# ERC128128FS_Breakout.net
KiCad netlist of a schematic drawn in EAGLE
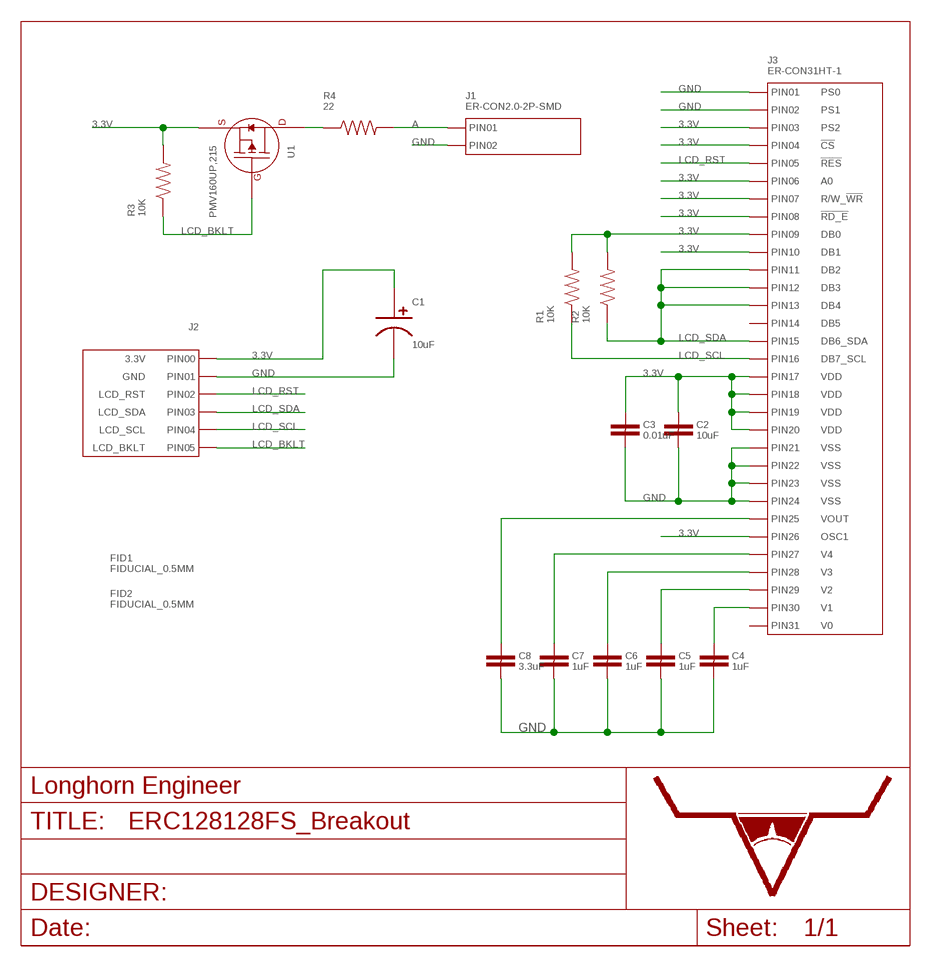
[diagram p0: schematic, sheet 1]

(export (version "E")
  (design (tool "Eeschema 10.0.6"))
  (components
    (comp (ref "C1")
      (value "10uF")
      (footprint "eagle-import:CP4MM")
      (libsource (lib "eagle-import") (part "CAPACITOR_P_4MM"))
    )
    (comp (ref "C2")
      (value "10uF")
      (footprint "eagle-import:1206")
      (libsource (lib "eagle-import") (part "CAPACITOR_NON_POLAR_1206"))
    )
    (comp (ref "C3")
      (value "0.01uF")
      (footprint "eagle-import:0603")
      (libsource (lib "eagle-import") (part "CAPACITOR_NON_POLAR_0603"))
    )
    (comp (ref "C4")
      (value "1uF")
      (footprint "eagle-import:0603")
      (libsource (lib "eagle-import") (part "CAPACITOR_NON_POLAR_0603"))
    )
    (comp (ref "C5")
      (value "1uF")
      (footprint "eagle-import:0603")
      (libsource (lib "eagle-import") (part "CAPACITOR_NON_POLAR_0603"))
    )
    (comp (ref "C6")
      (value "1uF")
      (footprint "eagle-import:0603")
      (libsource (lib "eagle-import") (part "CAPACITOR_NON_POLAR_0603"))
    )
    (comp (ref "C7")
      (value "1uF")
      (footprint "eagle-import:0603")
      (libsource (lib "eagle-import") (part "CAPACITOR_NON_POLAR_0603"))
    )
    (comp (ref "C8")
      (value "3.3uF")
      (footprint "eagle-import:0603")
      (libsource (lib "eagle-import") (part "CAPACITOR_NON_POLAR_0603"))
    )
    (comp (ref "FID1")
      (value "FIDUCIAL_0.5MM")
      (footprint "eagle-import:FIDUCIAL_0.5MM")
      (libsource (lib "eagle-import") (part "FIDUCIAL_0.5MM"))
    )
    (comp (ref "FID2")
      (value "FIDUCIAL_0.5MM")
      (footprint "eagle-import:FIDUCIAL_0.5MM")
      (libsource (lib "eagle-import") (part "FIDUCIAL_0.5MM"))
    )
    (comp (ref "J1")
      (value "ER-CON2.0-2P-SMD")
      (footprint "eagle-import:ER-CON2.0-2P-SMD")
      (libsource (lib "eagle-import") (part "CON_01X02_ER-CON2.0-2P-SMD"))
    )
    (comp (ref "J2")
      (value "HEADER_01X06_PTH_2.54MM")
      (footprint "eagle-import:PTH_2.54MM_01X06")
      (fields
        (field (name "LABEL00") "3.3V")
        (field (name "LABEL01") "GND")
        (field (name "LABEL02") "LCD_RST")
        (field (name "LABEL03") "LCD_SDA")
        (field (name "LABEL04") "LCD_SCL")
        (field (name "LABEL05") "LCD_BKLT")
      )
      (libsource (lib "eagle-import") (part "HEADER_01X06_PTH_2.54MM"))
    )
    (comp (ref "J3")
      (value "ER-CON31HT-1")
      (footprint "eagle-import:ER-CON31HT-1")
      (fields
        (field (name "LABEL01") "PS0")
        (field (name "LABEL02") "PS1")
        (field (name "LABEL03") "PS2")
        (field (name "LABEL04") "!CS")
        (field (name "LABEL05") "!RES")
        (field (name "LABEL06") "A0")
        (field (name "LABEL07") "R/W_!WR")
        (field (name "LABEL08") "!RD_E")
        (field (name "LABEL09") "DB0")
        (field (name "LABEL10") "DB1")
        (field (name "LABEL11") "DB2")
        (field (name "LABEL12") "DB3")
        (field (name "LABEL13") "DB4")
        (field (name "LABEL14") "DB5")
        (field (name "LABEL15") "DB6_SDA")
        (field (name "LABEL16") "DB7_SCL")
        (field (name "LABEL17") "VDD")
        (field (name "LABEL18") "VDD")
        (field (name "LABEL19") "VDD")
        (field (name "LABEL20") "VDD")
        (field (name "LABEL21") "VSS")
        (field (name "LABEL22") "VSS")
        (field (name "LABEL23") "VSS")
        (field (name "LABEL24") "VSS")
        (field (name "LABEL25") "VOUT")
        (field (name "LABEL26") "OSC1")
        (field (name "LABEL27") "V4")
        (field (name "LABEL28") "V3")
        (field (name "LABEL29") "V2")
        (field (name "LABEL30") "V1")
        (field (name "LABEL31") "V0")
      )
      (libsource (lib "eagle-import") (part "CON_01X31_ER-CON31HT-1"))
    )
    (comp (ref "R1")
      (value "10K")
      (footprint "eagle-import:0603")
      (libsource (lib "eagle-import") (part "RESISTOR_0603"))
    )
    (comp (ref "R2")
      (value "10K")
      (footprint "eagle-import:0603")
      (libsource (lib "eagle-import") (part "RESISTOR_0603"))
    )
    (comp (ref "R3")
      (value "10K")
      (footprint "eagle-import:0603")
      (libsource (lib "eagle-import") (part "RESISTOR_0603"))
    )
    (comp (ref "R4")
      (value "22")
      (footprint "eagle-import:0603")
      (libsource (lib "eagle-import") (part "RESISTOR_0603"))
    )
    (comp (ref "U$1")
      (value "LHE_FRAME")
      (footprint "eagle-import:LHE_FRAME")
      (fields (field (name "DNAME") "Parker Dillmann") (field (name "REVNUM") "REV: 2"))
      (libsource (lib "eagle-import") (part "LHE_FRAME"))
    )
    (comp (ref "U1")
      (value "PMV160UP,215")
      (footprint "eagle-import:SOT-23-3")
      (libsource (lib "eagle-import") (part "MOSFET_P-CHANNEL_SINGLE_SOT-23"))
    )
  )
  (nets
    (net (code "1") (name "/3.3V") (class "Default")
      (node (ref "C1") (pin "P$1") (pinfunction "P$1_P$1") (pintype "passive"))
      (node (ref "C2") (pin "1") (pinfunction "1_1") (pintype "passive"))
      (node (ref "C3") (pin "1") (pinfunction "1_1") (pintype "passive"))
      (node (ref "J2") (pin "P$1") (pinfunction "PIN0_P$1") (pintype "bidirectional"))
      (node (ref "J3") (pin "P$10") (pinfunction "PIN10_P$10") (pintype "bidirectional"))
      (node (ref "J3") (pin "P$17") (pinfunction "PIN17_P$17") (pintype "bidirectional"))
      (node (ref "J3") (pin "P$18") (pinfunction "PIN18_P$18") (pintype "bidirectional"))
      (node (ref "J3") (pin "P$19") (pinfunction "PIN19_P$19") (pintype "bidirectional"))
      (node (ref "J3") (pin "P$20") (pinfunction "PIN20_P$20") (pintype "bidirectional"))
      (node (ref "J3") (pin "P$26") (pinfunction "PIN26_P$26") (pintype "bidirectional"))
      (node (ref "J3") (pin "P$3") (pinfunction "PIN3_P$3") (pintype "bidirectional"))
      (node (ref "J3") (pin "P$4") (pinfunction "PIN4_P$4") (pintype "bidirectional"))
      (node (ref "J3") (pin "P$6") (pinfunction "PIN6_P$6") (pintype "bidirectional"))
      (node (ref "J3") (pin "P$7") (pinfunction "PIN7_P$7") (pintype "bidirectional"))
      (node (ref "J3") (pin "P$8") (pinfunction "PIN8_P$8") (pintype "bidirectional"))
      (node (ref "J3") (pin "P$9") (pinfunction "PIN9_P$9") (pintype "bidirectional"))
      (node (ref "R1") (pin "2") (pinfunction "2_2") (pintype "passive"))
      (node (ref "R2") (pin "2") (pinfunction "2_2") (pintype "passive"))
      (node (ref "R3") (pin "2") (pinfunction "2_2") (pintype "passive"))
      (node (ref "U1") (pin "2") (pinfunction "SOURCE_2") (pintype "bidirectional"))
    )
    (net (code "2") (name "/A") (class "Default")
      (node (ref "J1") (pin "P$1") (pinfunction "PIN1_P$1") (pintype "bidirectional"))
      (node (ref "R4") (pin "2") (pinfunction "2_2") (pintype "passive"))
    )
    (net (code "3") (name "/GND") (class "Default")
      (node (ref "C1") (pin "P$2") (pinfunction "P$2_P$2") (pintype "passive"))
      (node (ref "C2") (pin "2") (pinfunction "2_2") (pintype "passive"))
      (node (ref "C3") (pin "2") (pinfunction "2_2") (pintype "passive"))
      (node (ref "C4") (pin "2") (pinfunction "2_2") (pintype "passive"))
      (node (ref "C5") (pin "2") (pinfunction "2_2") (pintype "passive"))
      (node (ref "C6") (pin "2") (pinfunction "2_2") (pintype "passive"))
      (node (ref "C7") (pin "2") (pinfunction "2_2") (pintype "passive"))
      (node (ref "C8") (pin "2") (pinfunction "2_2") (pintype "passive"))
      (node (ref "J1") (pin "P$2") (pinfunction "PIN2_P$2") (pintype "bidirectional"))
      (node (ref "J2") (pin "P$2") (pinfunction "PIN1_P$2") (pintype "bidirectional"))
      (node (ref "J3") (pin "P$1") (pinfunction "PIN1_P$1") (pintype "bidirectional"))
      (node (ref "J3") (pin "P$2") (pinfunction "PIN2_P$2") (pintype "bidirectional"))
      (node (ref "J3") (pin "P$21") (pinfunction "PIN21_P$21") (pintype "bidirectional"))
      (node (ref "J3") (pin "P$22") (pinfunction "PIN22_P$22") (pintype "bidirectional"))
      (node (ref "J3") (pin "P$23") (pinfunction "PIN23_P$23") (pintype "bidirectional"))
      (node (ref "J3") (pin "P$24") (pinfunction "PIN24_P$24") (pintype "bidirectional"))
    )
    (net (code "4") (name "/LCD_BKLT") (class "Default")
      (node (ref "J2") (pin "P$6") (pinfunction "PIN5_P$6") (pintype "bidirectional"))
      (node (ref "R3") (pin "1") (pinfunction "1_1") (pintype "passive"))
      (node (ref "U1") (pin "1") (pinfunction "GATE_1") (pintype "bidirectional"))
    )
    (net (code "5") (name "/LCD_RST") (class "Default")
      (node (ref "J2") (pin "P$3") (pinfunction "PIN2_P$3") (pintype "bidirectional"))
      (node (ref "J3") (pin "P$5") (pinfunction "PIN5_P$5") (pintype "bidirectional"))
    )
    (net (code "6") (name "/LCD_SCL") (class "Default")
      (node (ref "J2") (pin "P$5") (pinfunction "PIN4_P$5") (pintype "bidirectional"))
      (node (ref "J3") (pin "P$16") (pinfunction "PIN16_P$16") (pintype "bidirectional"))
      (node (ref "R1") (pin "1") (pinfunction "1_1") (pintype "passive"))
    )
    (net (code "7") (name "/LCD_SDA") (class "Default")
      (node (ref "J2") (pin "P$4") (pinfunction "PIN3_P$4") (pintype "bidirectional"))
      (node (ref "J3") (pin "P$11") (pinfunction "PIN11_P$11") (pintype "bidirectional"))
      (node (ref "J3") (pin "P$12") (pinfunction "PIN12_P$12") (pintype "bidirectional"))
      (node (ref "J3") (pin "P$13") (pinfunction "PIN13_P$13") (pintype "bidirectional"))
      (node (ref "J3") (pin "P$15") (pinfunction "PIN15_P$15") (pintype "bidirectional"))
      (node (ref "R2") (pin "1") (pinfunction "1_1") (pintype "passive"))
    )
    (net (code "8") (name "Net-(J3-PIN25)") (class "Default")
      (node (ref "C8") (pin "1") (pinfunction "1_1") (pintype "passive"))
      (node (ref "J3") (pin "P$25") (pinfunction "PIN25_P$25") (pintype "bidirectional"))
    )
    (net (code "9") (name "Net-(J3-PIN27)") (class "Default")
      (node (ref "C7") (pin "1") (pinfunction "1_1") (pintype "passive"))
      (node (ref "J3") (pin "P$27") (pinfunction "PIN27_P$27") (pintype "bidirectional"))
    )
    (net (code "10") (name "Net-(J3-PIN28)") (class "Default")
      (node (ref "C6") (pin "1") (pinfunction "1_1") (pintype "passive"))
      (node (ref "J3") (pin "P$28") (pinfunction "PIN28_P$28") (pintype "bidirectional"))
    )
    (net (code "11") (name "Net-(J3-PIN29)") (class "Default")
      (node (ref "C5") (pin "1") (pinfunction "1_1") (pintype "passive"))
      (node (ref "J3") (pin "P$29") (pinfunction "PIN29_P$29") (pintype "bidirectional"))
    )
    (net (code "12") (name "Net-(J3-PIN30)") (class "Default")
      (node (ref "C4") (pin "1") (pinfunction "1_1") (pintype "passive"))
      (node (ref "J3") (pin "P$30") (pinfunction "PIN30_P$30") (pintype "bidirectional"))
    )
    (net (code "13") (name "Net-(U1-DRAIN)") (class "Default")
      (node (ref "R4") (pin "1") (pinfunction "1_1") (pintype "passive"))
      (node (ref "U1") (pin "3") (pinfunction "DRAIN_3") (pintype "bidirectional"))
    )
    (net (code "14") (name "unconnected-(J3-PIN14-PadP$14)") (class "Default")
      (node (ref "J3") (pin "P$14") (pinfunction "PIN14_P$14") (pintype "bidirectional"))
    )
    (net (code "15") (name "unconnected-(J3-PIN31-PadP$31)") (class "Default")
      (node (ref "J3") (pin "P$31") (pinfunction "PIN31_P$31") (pintype "bidirectional"))
    )
  )
)
